# Nusbio_2-FT232BreakOut.net
KiCad netlist of a schematic drawn in EAGLE
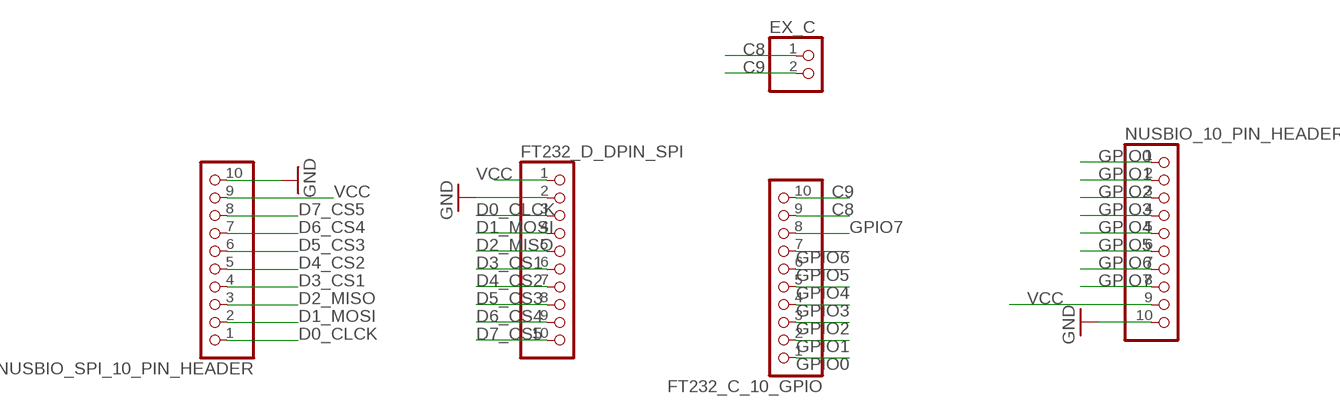
[diagram p0: schematic, sheet 1]

(export (version "E")
  (design (tool "Eeschema 10.0.6"))
  (components
    (comp (ref "EX_C")
      (value "PINHD-1X2")
      (footprint "eagle-import:1X02")
      (libsource (lib "eagle-import") (part "PINHD-1X2"))
    )
    (comp (ref "FT232_C_10_GPIO")
      (value "PINHD-1X10")
      (footprint "eagle-import:1X10")
      (libsource (lib "eagle-import") (part "PINHD-1X10"))
    )
    (comp (ref "FT232_D_DPIN_SPI")
      (value "PINHD-1X10")
      (footprint "eagle-import:1X10")
      (libsource (lib "eagle-import") (part "PINHD-1X10"))
    )
    (comp (ref "NUSBIO_10_PIN_HEADER")
      (value "PINHD-1X10")
      (footprint "eagle-import:1X10")
      (libsource (lib "eagle-import") (part "PINHD-1X10"))
    )
    (comp (ref "NUSBIO_SPI_10_PIN_HEADER")
      (value "PINHD-1X10")
      (footprint "eagle-import:1X10")
      (libsource (lib "eagle-import") (part "PINHD-1X10"))
    )
  )
  (nets
    (net (code "1") (name "/C8") (class "Default")
      (node (ref "EX_C") (pin "1") (pinfunction "1_1") (pintype "passive"))
      (node (ref "FT232_C_10_GPIO") (pin "9") (pinfunction "9_9") (pintype "passive"))
    )
    (net (code "2") (name "/C9") (class "Default")
      (node (ref "EX_C") (pin "2") (pinfunction "2_2") (pintype "passive"))
      (node (ref "FT232_C_10_GPIO") (pin "10") (pinfunction "10_10") (pintype "passive"))
    )
    (net (code "3") (name "/D0_CLCK") (class "Default")
      (node (ref "FT232_D_DPIN_SPI") (pin "3") (pinfunction "3_3") (pintype "passive"))
      (node (ref "NUSBIO_SPI_10_PIN_HEADER") (pin "1") (pinfunction "1_1") (pintype "passive"))
    )
    (net (code "4") (name "/D1_MOSI") (class "Default")
      (node (ref "FT232_D_DPIN_SPI") (pin "4") (pinfunction "4_4") (pintype "passive"))
      (node (ref "NUSBIO_SPI_10_PIN_HEADER") (pin "2") (pinfunction "2_2") (pintype "passive"))
    )
    (net (code "5") (name "/D2_MISO") (class "Default")
      (node (ref "FT232_D_DPIN_SPI") (pin "5") (pinfunction "5_5") (pintype "passive"))
      (node (ref "NUSBIO_SPI_10_PIN_HEADER") (pin "3") (pinfunction "3_3") (pintype "passive"))
    )
    (net (code "6") (name "/D3_CS1") (class "Default")
      (node (ref "FT232_D_DPIN_SPI") (pin "6") (pinfunction "6_6") (pintype "passive"))
      (node (ref "NUSBIO_SPI_10_PIN_HEADER") (pin "4") (pinfunction "4_4") (pintype "passive"))
    )
    (net (code "7") (name "/D4_CS2") (class "Default")
      (node (ref "FT232_D_DPIN_SPI") (pin "7") (pinfunction "7_7") (pintype "passive"))
      (node (ref "NUSBIO_SPI_10_PIN_HEADER") (pin "5") (pinfunction "5_5") (pintype "passive"))
    )
    (net (code "8") (name "/D5_CS3") (class "Default")
      (node (ref "FT232_D_DPIN_SPI") (pin "8") (pinfunction "8_8") (pintype "passive"))
      (node (ref "NUSBIO_SPI_10_PIN_HEADER") (pin "6") (pinfunction "6_6") (pintype "passive"))
    )
    (net (code "9") (name "/D6_CS4") (class "Default")
      (node (ref "FT232_D_DPIN_SPI") (pin "9") (pinfunction "9_9") (pintype "passive"))
      (node (ref "NUSBIO_SPI_10_PIN_HEADER") (pin "7") (pinfunction "7_7") (pintype "passive"))
    )
    (net (code "10") (name "/D7_CS5") (class "Default")
      (node (ref "FT232_D_DPIN_SPI") (pin "10") (pinfunction "10_10") (pintype "passive"))
      (node (ref "NUSBIO_SPI_10_PIN_HEADER") (pin "8") (pinfunction "8_8") (pintype "passive"))
    )
    (net (code "11") (name "/GPIO0") (class "Default")
      (node (ref "FT232_C_10_GPIO") (pin "1") (pinfunction "1_1") (pintype "passive"))
      (node (ref "NUSBIO_10_PIN_HEADER") (pin "1") (pinfunction "1_1") (pintype "passive"))
    )
    (net (code "12") (name "/GPIO1") (class "Default")
      (node (ref "FT232_C_10_GPIO") (pin "2") (pinfunction "2_2") (pintype "passive"))
      (node (ref "NUSBIO_10_PIN_HEADER") (pin "2") (pinfunction "2_2") (pintype "passive"))
    )
    (net (code "13") (name "/GPIO2") (class "Default")
      (node (ref "FT232_C_10_GPIO") (pin "3") (pinfunction "3_3") (pintype "passive"))
      (node (ref "NUSBIO_10_PIN_HEADER") (pin "3") (pinfunction "3_3") (pintype "passive"))
    )
    (net (code "14") (name "/GPIO3") (class "Default")
      (node (ref "FT232_C_10_GPIO") (pin "4") (pinfunction "4_4") (pintype "passive"))
      (node (ref "NUSBIO_10_PIN_HEADER") (pin "4") (pinfunction "4_4") (pintype "passive"))
    )
    (net (code "15") (name "/GPIO4") (class "Default")
      (node (ref "FT232_C_10_GPIO") (pin "5") (pinfunction "5_5") (pintype "passive"))
      (node (ref "NUSBIO_10_PIN_HEADER") (pin "5") (pinfunction "5_5") (pintype "passive"))
    )
    (net (code "16") (name "/GPIO5") (class "Default")
      (node (ref "FT232_C_10_GPIO") (pin "6") (pinfunction "6_6") (pintype "passive"))
      (node (ref "NUSBIO_10_PIN_HEADER") (pin "6") (pinfunction "6_6") (pintype "passive"))
    )
    (net (code "17") (name "/GPIO6") (class "Default")
      (node (ref "FT232_C_10_GPIO") (pin "7") (pinfunction "7_7") (pintype "passive"))
      (node (ref "NUSBIO_10_PIN_HEADER") (pin "7") (pinfunction "7_7") (pintype "passive"))
    )
    (net (code "18") (name "/GPIO7") (class "Default")
      (node (ref "FT232_C_10_GPIO") (pin "8") (pinfunction "8_8") (pintype "passive"))
      (node (ref "NUSBIO_10_PIN_HEADER") (pin "8") (pinfunction "8_8") (pintype "passive"))
    )
    (net (code "19") (name "/VCC") (class "Default")
      (node (ref "FT232_D_DPIN_SPI") (pin "1") (pinfunction "1_1") (pintype "passive"))
      (node (ref "NUSBIO_10_PIN_HEADER") (pin "9") (pinfunction "9_9") (pintype "passive"))
      (node (ref "NUSBIO_SPI_10_PIN_HEADER") (pin "9") (pinfunction "9_9") (pintype "passive"))
    )
    (net (code "20") (name "GND") (class "Default")
      (node (ref "FT232_D_DPIN_SPI") (pin "2") (pinfunction "2_2") (pintype "passive"))
      (node (ref "NUSBIO_10_PIN_HEADER") (pin "10") (pinfunction "10_10") (pintype "passive"))
      (node (ref "NUSBIO_SPI_10_PIN_HEADER") (pin "10") (pinfunction "10_10") (pintype "passive"))
    )
  )
)
